# activity_tracker.net
KiCad netlist of a schematic drawn in Altium Designer
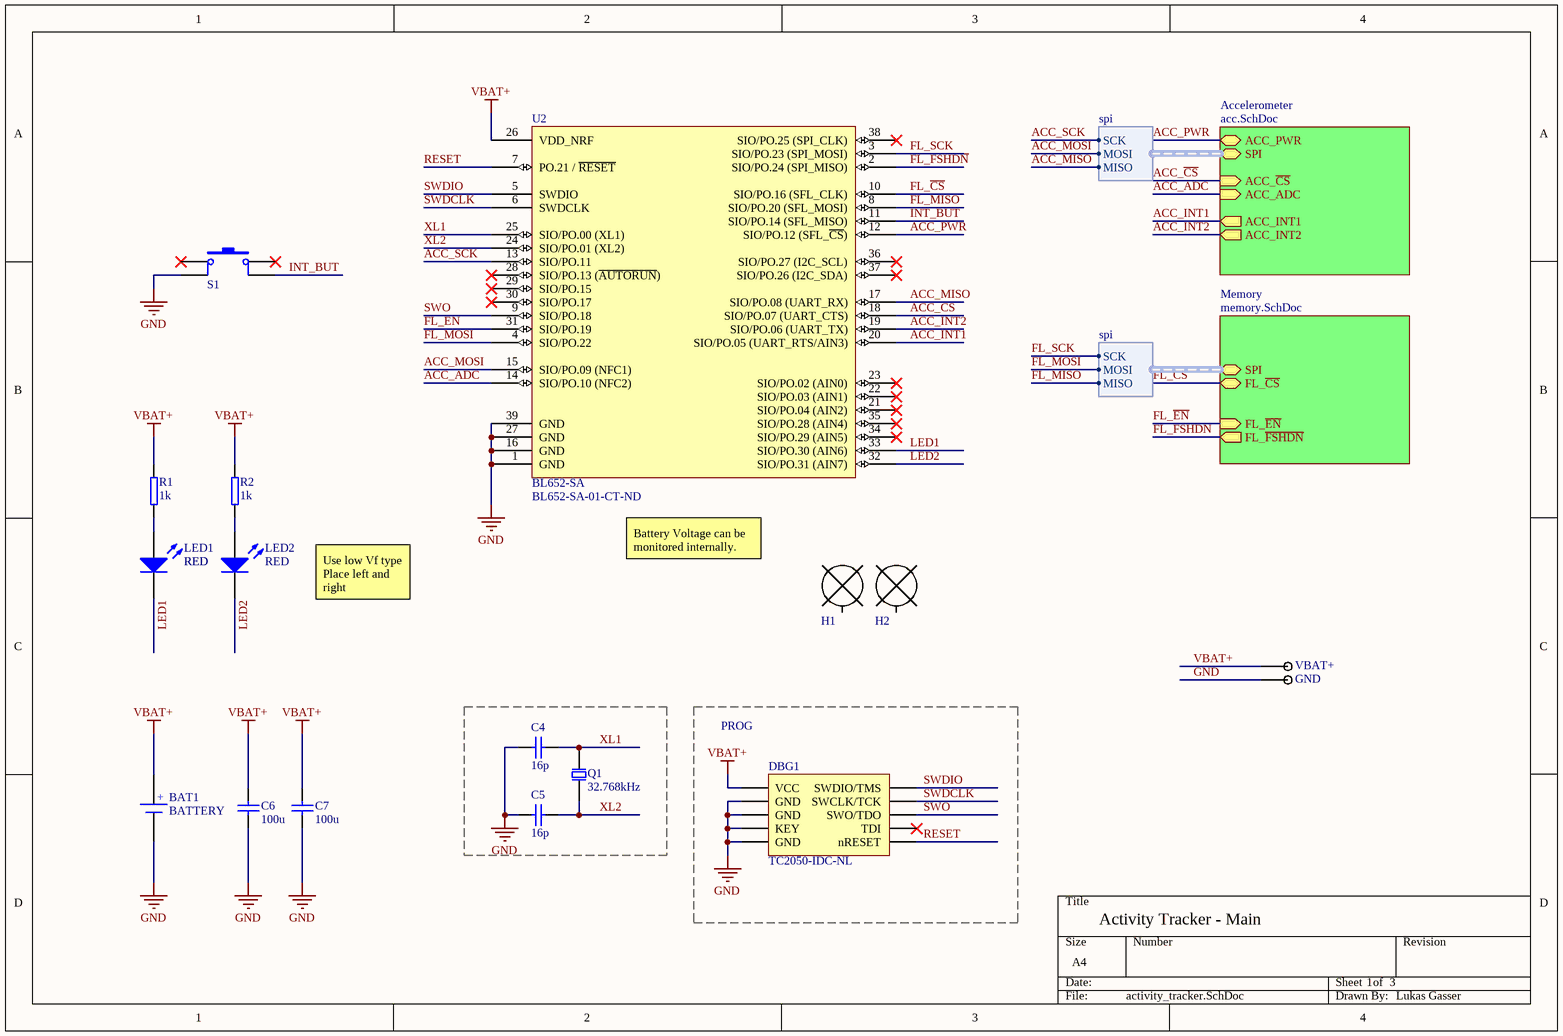
[diagram p0: activity_tracker.SchDoc]

(export (version "E")
  (design (tool "Eeschema 10.0.6"))
  (components
    (comp (ref "BAT1")
      (value "BATTERY")
      (footprint "BK-912_MIN_FP")
      (description "Battery")
      (libsource (lib "battery") (part "BATTERY"))
    )
    (comp (ref "C4")
      (value "16p")
      (footprint "CAPC1608X95N")
      (description "Capacitor")
      (fields (field (name "VOLTAGE") "50V"))
      (libsource (lib "rlc") (part "C"))
    )
    (comp (ref "C5")
      (value "16p")
      (footprint "CAPC1608X95N")
      (description "Capacitor")
      (fields (field (name "VOLTAGE") "50V"))
      (libsource (lib "rlc") (part "C"))
    )
    (comp (ref "C6")
      (value "100u")
      (footprint "CAPC3216X18N")
      (description "Capacitor")
      (fields (field (name "VOLTAGE") "6V3"))
      (libsource (lib "rlc") (part "C"))
    )
    (comp (ref "C7")
      (value "100u")
      (footprint "CAPC3216X18N")
      (description "Capacitor")
      (fields (field (name "VOLTAGE") "6V3"))
      (libsource (lib "rlc") (part "C"))
    )
    (comp (ref "DBG1")
      (value "TC2050-IDC-NL")
      (footprint "TC2050-IDC-NL")
      (description "ARM Mini JTAG / SWD 10-pin connector")
      (libsource (lib "icsp_debug-connectors") (part "TC2050-IDC-NL"))
    )
    (comp (ref "GND")
      (value "Testpoint")
      (footprint "POGO1")
      (libsource (lib "connector") (part "Testpoint"))
    )
    (comp (ref "H1")
      (value "HOLE")
      (footprint "M1_SMALL_NOKEEPOUT")
      (description "Hole")
      (libsource (lib "misc") (part "HOLE"))
    )
    (comp (ref "H2")
      (value "HOLE")
      (footprint "M1_SMALL_NOKEEPOUT")
      (description "Hole")
      (libsource (lib "misc") (part "HOLE"))
    )
    (comp (ref "LED1")
      (value "RED")
      (footprint "LED0603")
      (description "LED")
      (fields (field (name "COLOR") "RED"))
      (libsource (lib "led") (part "LED"))
    )
    (comp (ref "LED2")
      (value "RED")
      (footprint "LED0603")
      (description "LED")
      (libsource (lib "led") (part "LED"))
    )
    (comp (ref "Q1")
      (value "32.768kHz")
      (footprint "ABS06")
      (description "Crystal")
      (libsource (lib "crystal") (part "Q-0Shield"))
    )
    (comp (ref "R1")
      (value "1k")
      (footprint "RESC1608X55N")
      (description "Resistor")
      (libsource (lib "rlc") (part "R"))
    )
    (comp (ref "R2")
      (value "1k")
      (footprint "RESC1608X55N")
      (description "Resistor")
      (libsource (lib "rlc") (part "R"))
    )
    (comp (ref "S1")
      (value "SW-PB-4T")
      (footprint "TL3315NF250Q")
      (description "Tact switch")
      (libsource (lib "switch") (part "SW-PB-4T"))
    )
    (comp (ref "U2")
      (value "BL652-SA")
      (footprint "BL652-SA_NO_KEEPOUT")
      (description "RF TXRX MOD BLUETOOTH INT ANT")
      (fields (field (name "SUPPLIER PART NUMBER 1") "BL652-SA-01-CT-ND"))
      (libsource (lib "bluetooth") (part "BL652-SA"))
    )
    (comp (ref "VBAT+")
      (value "Testpoint")
      (footprint "POGO1")
      (libsource (lib "connector") (part "Testpoint"))
    )
  )
  (nets
    (net (code "2") (name "/ACC_ADC") (class "Default")
      (node (ref "U2") (pin "14") (pinfunction "SIO/PO.10_(NFC2)_14") (pintype "bidirectional"))
    )
    (net (code "3") (name "/ACC_INT1") (class "Default")
      (node (ref "U2") (pin "20") (pinfunction "SIO/PO.05_(UART_RTS/AIN3)_20") (pintype "bidirectional"))
    )
    (net (code "4") (name "/ACC_INT2") (class "Default")
      (node (ref "U2") (pin "19") (pinfunction "SIO/PO.06_(UART_TX)_19") (pintype "bidirectional"))
    )
    (net (code "5") (name "/ACC_MISO") (class "Default")
      (node (ref "U2") (pin "17") (pinfunction "SIO/PO.08_(UART_RX)_17") (pintype "bidirectional"))
    )
    (net (code "6") (name "/ACC_MOSI") (class "Default")
      (node (ref "U2") (pin "15") (pinfunction "SIO/PO.09_(NFC1)_15") (pintype "bidirectional"))
    )
    (net (code "7") (name "/ACC_PWR") (class "Default")
      (node (ref "U2") (pin "12") (pinfunction "SIO/PO.12_(SFL_~{CS})_12") (pintype "bidirectional"))
    )
    (net (code "8") (name "/ACC_SCK") (class "Default")
      (node (ref "U2") (pin "13") (pinfunction "SIO/PO.11_13") (pintype "bidirectional"))
    )
    (net (code "9") (name "/ACC_~{CS}") (class "Default")
      (node (ref "U2") (pin "18") (pinfunction "SIO/PO.07_(UART_CTS)_18") (pintype "bidirectional"))
    )
    (net (code "10") (name "/FL_MISO") (class "Default")
      (node (ref "U2") (pin "8") (pinfunction "SIO/PO.20_(SFL_MOSI)_8") (pintype "bidirectional"))
    )
    (net (code "11") (name "/FL_MOSI") (class "Default")
      (node (ref "U2") (pin "4") (pinfunction "SIO/PO.22_4") (pintype "bidirectional"))
    )
    (net (code "12") (name "/FL_SCK") (class "Default")
      (node (ref "U2") (pin "3") (pinfunction "SIO/PO.23_(SPI_MOSI)_3") (pintype "bidirectional"))
    )
    (net (code "13") (name "/FL_~{CS}") (class "Default")
      (node (ref "U2") (pin "10") (pinfunction "SIO/PO.16_(SFL_CLK)_10") (pintype "bidirectional"))
    )
    (net (code "14") (name "/FL_~{EN}") (class "Default")
      (node (ref "U2") (pin "31") (pinfunction "SIO/PO.19_31") (pintype "bidirectional"))
    )
    (net (code "15") (name "/FL_~{FSHDN}") (class "Default")
      (node (ref "U2") (pin "2") (pinfunction "SIO/PO.24_(SPI_MISO)_2") (pintype "bidirectional"))
    )
    (net (code "16") (name "/INT_BUT") (class "Default")
      (node (ref "S1") (pin "4") (pinfunction "4_4") (pintype "passive"))
      (node (ref "U2") (pin "11") (pinfunction "SIO/PO.14_(SFL_MISO)_11") (pintype "bidirectional"))
    )
    (net (code "17") (name "/LED1") (class "Default")
      (node (ref "LED1") (pin "2") (pinfunction "K_2") (pintype "passive"))
      (node (ref "U2") (pin "33") (pinfunction "SIO/PO.30_(AIN6)_33") (pintype "bidirectional"))
    )
    (net (code "18") (name "/LED2") (class "Default")
      (node (ref "LED2") (pin "2") (pinfunction "K_2") (pintype "passive"))
      (node (ref "U2") (pin "32") (pinfunction "SIO/PO.31_(AIN7)_32") (pintype "bidirectional"))
    )
    (net (code "19") (name "/RESET") (class "Default")
      (node (ref "DBG1") (pin "10") (pinfunction "nRESET_10") (pintype "passive"))
      (node (ref "U2") (pin "7") (pinfunction "PO.21_/_~{RESET}_7") (pintype "bidirectional"))
    )
    (net (code "20") (name "/SWDCLK") (class "Default")
      (node (ref "DBG1") (pin "4") (pinfunction "SWCLK/TCK_4") (pintype "passive"))
      (node (ref "U2") (pin "6") (pinfunction "SWDCLK_6") (pintype "passive"))
    )
    (net (code "21") (name "/SWDIO") (class "Default")
      (node (ref "DBG1") (pin "2") (pinfunction "SWDIO/TMS_2") (pintype "passive"))
      (node (ref "U2") (pin "5") (pinfunction "SWDIO_5") (pintype "passive"))
    )
    (net (code "22") (name "/SWO") (class "Default")
      (node (ref "DBG1") (pin "6") (pinfunction "SWO/TDO_6") (pintype "passive"))
      (node (ref "U2") (pin "9") (pinfunction "SIO/PO.18_9") (pintype "bidirectional"))
    )
    (net (code "23") (name "/XL1") (class "Default")
      (node (ref "C4") (pin "2") (pinfunction "2_2") (pintype "passive"))
      (node (ref "Q1") (pin "2") (pinfunction "2_2") (pintype "passive"))
      (node (ref "U2") (pin "25") (pinfunction "SIO/PO.00_(XL1)_25") (pintype "bidirectional"))
    )
    (net (code "24") (name "/XL2") (class "Default")
      (node (ref "C5") (pin "2") (pinfunction "2_2") (pintype "passive"))
      (node (ref "Q1") (pin "1") (pinfunction "1_1") (pintype "passive"))
      (node (ref "U2") (pin "24") (pinfunction "SIO/PO.01_(XL2)_24") (pintype "bidirectional"))
    )
    (net (code "26") (name "GND") (class "Default")
      (node (ref "BAT1") (pin "-") (pinfunction "-_-") (pintype "power_in"))
      (node (ref "C4") (pin "1") (pinfunction "1_1") (pintype "passive"))
      (node (ref "C5") (pin "1") (pinfunction "1_1") (pintype "passive"))
      (node (ref "C6") (pin "1") (pinfunction "1_1") (pintype "passive"))
      (node (ref "C7") (pin "1") (pinfunction "1_1") (pintype "passive"))
      (node (ref "DBG1") (pin "3") (pinfunction "GND_3") (pintype "power_in"))
      (node (ref "DBG1") (pin "5") (pinfunction "GND_5") (pintype "power_in"))
      (node (ref "DBG1") (pin "7") (pinfunction "KEY_7") (pintype "passive"))
      (node (ref "DBG1") (pin "9") (pinfunction "GND_9") (pintype "power_in"))
      (node (ref "GND") (pin "1") (pinfunction "1_1") (pintype "passive"))
      (node (ref "S1") (pin "2") (pinfunction "2_2") (pintype "passive"))
      (node (ref "U2") (pin "1") (pinfunction "GND_1") (pintype "passive"))
      (node (ref "U2") (pin "16") (pinfunction "GND_16") (pintype "passive"))
      (node (ref "U2") (pin "27") (pinfunction "GND_27") (pintype "passive"))
      (node (ref "U2") (pin "39") (pinfunction "GND_39") (pintype "passive"))
    )
    (net (code "27") (name "Net-(LED1-A)") (class "Default")
      (node (ref "LED1") (pin "1") (pinfunction "A_1") (pintype "passive"))
      (node (ref "R1") (pin "1") (pinfunction "1_1") (pintype "passive"))
    )
    (net (code "28") (name "Net-(LED2-A)") (class "Default")
      (node (ref "LED2") (pin "1") (pinfunction "A_1") (pintype "passive"))
      (node (ref "R2") (pin "1") (pinfunction "1_1") (pintype "passive"))
    )
    (net (code "29") (name "VBAT+") (class "Default")
      (node (ref "BAT1") (pin "+") (pinfunction "+_+") (pintype "power_in"))
      (node (ref "C6") (pin "2") (pinfunction "2_2") (pintype "passive"))
      (node (ref "C7") (pin "2") (pinfunction "2_2") (pintype "passive"))
      (node (ref "DBG1") (pin "1") (pinfunction "VCC_1") (pintype "power_in"))
      (node (ref "R1") (pin "2") (pinfunction "2_2") (pintype "passive"))
      (node (ref "R2") (pin "2") (pinfunction "2_2") (pintype "passive"))
      (node (ref "U2") (pin "26") (pinfunction "VDD_NRF_26") (pintype "passive"))
      (node (ref "VBAT+") (pin "1") (pinfunction "1_1") (pintype "passive"))
    )
    (net (code "30") (name "unconnected-(DBG1-TDI-Pad8)") (class "Default")
      (node (ref "DBG1") (pin "8") (pinfunction "TDI_8") (pintype "passive+no_connect"))
    )
    (net (code "31") (name "unconnected-(H1-PadH)") (class "Default")
      (node (ref "H1") (pin "H") (pinfunction "H_H") (pintype "passive"))
    )
    (net (code "32") (name "unconnected-(H2-PadH)") (class "Default")
      (node (ref "H2") (pin "H") (pinfunction "H_H") (pintype "passive"))
    )
    (net (code "33") (name "unconnected-(S1-Pad1)") (class "Default")
      (node (ref "S1") (pin "1") (pinfunction "1_1") (pintype "passive+no_connect"))
    )
    (net (code "34") (name "unconnected-(S1-Pad3)") (class "Default")
      (node (ref "S1") (pin "3") (pinfunction "3_3") (pintype "passive+no_connect"))
    )
    (net (code "35") (name "unconnected-(U2-SIO{slash}PO.02_(AIN0)-Pad23)") (class "Default")
      (node (ref "U2") (pin "23") (pinfunction "SIO/PO.02_(AIN0)_23") (pintype "bidirectional+no_connect"))
    )
    (net (code "36") (name "unconnected-(U2-SIO{slash}PO.03_(AIN1)-Pad22)") (class "Default")
      (node (ref "U2") (pin "22") (pinfunction "SIO/PO.03_(AIN1)_22") (pintype "bidirectional+no_connect"))
    )
    (net (code "37") (name "unconnected-(U2-SIO{slash}PO.04_(AIN2)-Pad21)") (class "Default")
      (node (ref "U2") (pin "21") (pinfunction "SIO/PO.04_(AIN2)_21") (pintype "bidirectional+no_connect"))
    )
    (net (code "38") (name "unconnected-(U2-SIO{slash}PO.13_(~{AUTORUN})-Pad28)") (class "Default")
      (node (ref "U2") (pin "28") (pinfunction "SIO/PO.13_(~{AUTORUN})_28") (pintype "bidirectional+no_connect"))
    )
    (net (code "39") (name "unconnected-(U2-SIO{slash}PO.15-Pad29)") (class "Default")
      (node (ref "U2") (pin "29") (pinfunction "SIO/PO.15_29") (pintype "bidirectional+no_connect"))
    )
    (net (code "40") (name "unconnected-(U2-SIO{slash}PO.17-Pad30)") (class "Default")
      (node (ref "U2") (pin "30") (pinfunction "SIO/PO.17_30") (pintype "bidirectional+no_connect"))
    )
    (net (code "41") (name "unconnected-(U2-SIO{slash}PO.25_(SPI_CLK)-Pad38)") (class "Default")
      (node (ref "U2") (pin "38") (pinfunction "SIO/PO.25_(SPI_CLK)_38") (pintype "bidirectional+no_connect"))
    )
    (net (code "42") (name "unconnected-(U2-SIO{slash}PO.26_(I2C_SDA)-Pad37)") (class "Default")
      (node (ref "U2") (pin "37") (pinfunction "SIO/PO.26_(I2C_SDA)_37") (pintype "bidirectional+no_connect"))
    )
    (net (code "43") (name "unconnected-(U2-SIO{slash}PO.27_(I2C_SCL)-Pad36)") (class "Default")
      (node (ref "U2") (pin "36") (pinfunction "SIO/PO.27_(I2C_SCL)_36") (pintype "bidirectional+no_connect"))
    )
    (net (code "44") (name "unconnected-(U2-SIO{slash}PO.28_(AIN4)-Pad35)") (class "Default")
      (node (ref "U2") (pin "35") (pinfunction "SIO/PO.28_(AIN4)_35") (pintype "bidirectional+no_connect"))
    )
    (net (code "45") (name "unconnected-(U2-SIO{slash}PO.29_(AIN5)-Pad34)") (class "Default")
      (node (ref "U2") (pin "34") (pinfunction "SIO/PO.29_(AIN5)_34") (pintype "bidirectional+no_connect"))
    )
  )
)
